# Moo_Sensors.net
KiCad netlist of a schematic drawn in Altium Designer
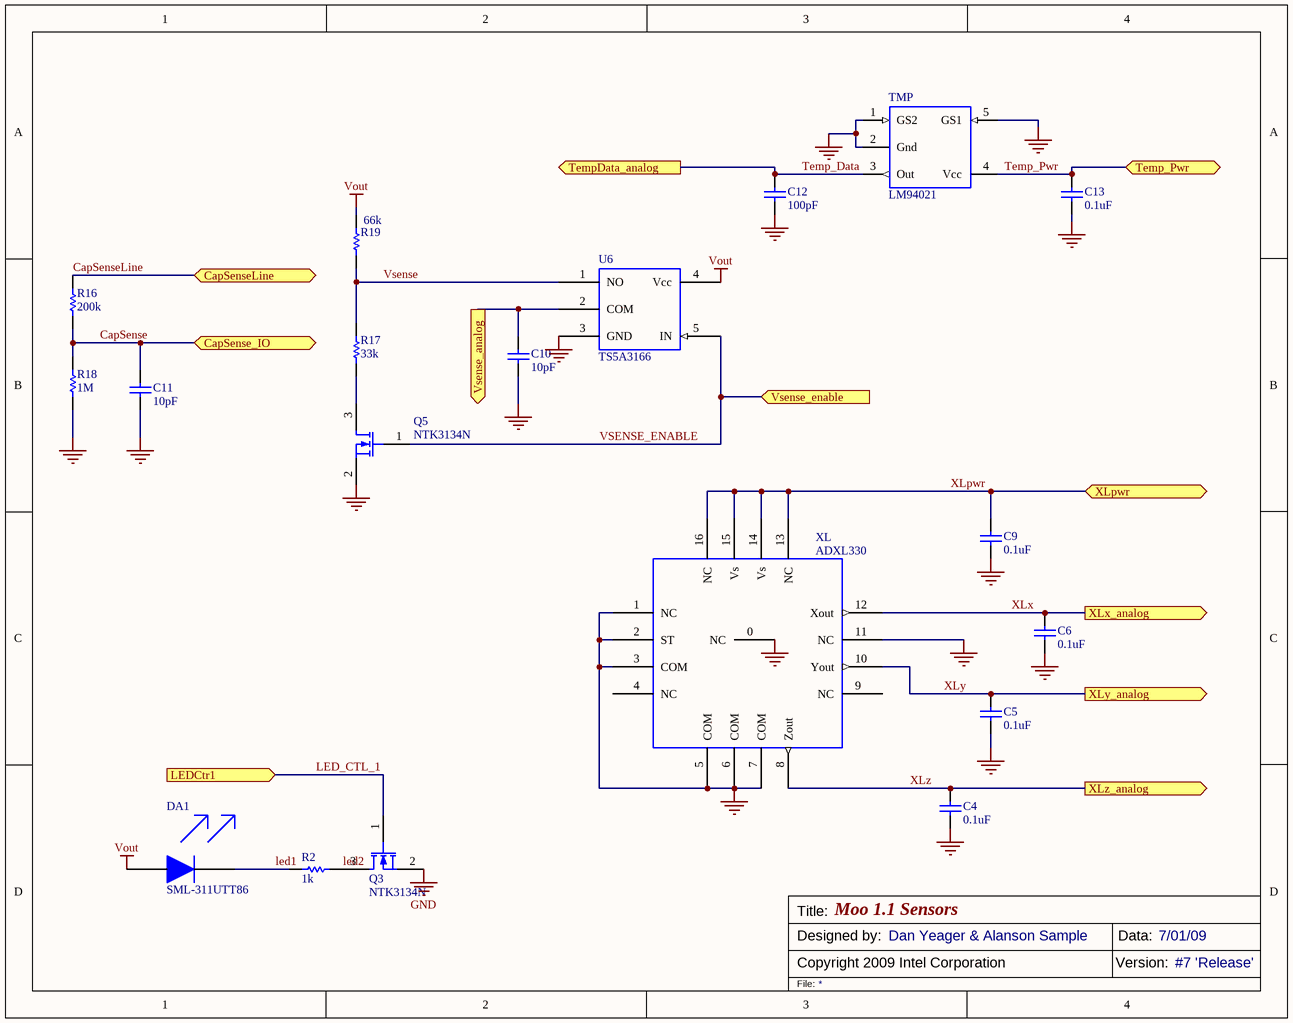
[diagram p0: Moo_Sensors.SchDoc]

(export (version "E")
  (design (tool "Eeschema 10.0.6"))
  (components
    (comp (ref "C4")
      (value "0.1uF")
      (footprint "WispLib:0402")
      (description "Ceramic Capacitor - Standard")
      (fields (field (name "Comment") "Ceramic_Chip_Capacitor"))
      (libsource (lib "WispLib") (part "Ceramic_Chip_Capacitor"))
    )
    (comp (ref "C5")
      (value "0.1uF")
      (footprint "WispLib:0402")
      (description "Ceramic Capacitor - Standard")
      (fields (field (name "Comment") "Ceramic_Chip_Capacitor"))
      (libsource (lib "WispLib") (part "Ceramic_Chip_Capacitor"))
    )
    (comp (ref "C6")
      (value "0.1uF")
      (footprint "WispLib:0402")
      (description "Ceramic Capacitor - Standard")
      (fields (field (name "Comment") "Ceramic_Chip_Capacitor"))
      (libsource (lib "WispLib") (part "Ceramic_Chip_Capacitor"))
    )
    (comp (ref "C9")
      (value "0.1uF")
      (footprint "WispLib:0402")
      (description "Ceramic Capacitor - Standard")
      (fields (field (name "Comment") "Ceramic_Chip_Capacitor"))
      (libsource (lib "WispLib") (part "Ceramic_Chip_Capacitor"))
    )
    (comp (ref "C10")
      (value "10pF")
      (footprint "WispLib:0402")
      (description "Ceramic Capacitor - Standard")
      (fields (field (name "Comment") "Ceramic_Chip_Capacitor"))
      (libsource (lib "WispLib") (part "Ceramic_Chip_Capacitor"))
    )
    (comp (ref "C11")
      (value "10pF")
      (footprint "WispLib:0402")
      (description "Ceramic Capacitor - Standard")
      (fields (field (name "Comment") "Ceramic_Chip_Capacitor"))
      (libsource (lib "WispLib") (part "Ceramic_Chip_Capacitor"))
    )
    (comp (ref "C12")
      (value "100pF")
      (footprint "WispLib:0402")
      (description "Ceramic Capacitor - Standard")
      (fields (field (name "Comment") "Ceramic_Chip_Capacitor"))
      (libsource (lib "WispLib") (part "Ceramic_Chip_Capacitor"))
    )
    (comp (ref "C13")
      (value "0.1uF")
      (footprint "WispLib:0402")
      (description "Ceramic Capacitor - Standard")
      (fields (field (name "Comment") "Ceramic_Chip_Capacitor"))
      (libsource (lib "WispLib") (part "Ceramic_Chip_Capacitor"))
    )
    (comp (ref "DA1")
      (value "SML-311UTT86")
      (footprint "LED-0603")
      (description "LED 630NM RED WTR CLR 0603 SMD")
      (libsource (lib "WispLib") (part "SML-311UTT86"))
    )
    (comp (ref "Q3")
      (value "NTK3134N")
      (footprint "SOT723")
      (description "Powe Mosfet 20V, 890mA, Single N-channel")
      (libsource (lib "WispLib") (part "NTK3134N"))
    )
    (comp (ref "Q5")
      (value "NTK3134N")
      (footprint "SOT723")
      (description "Powe Mosfet 20V, 890mA, Single N-channel")
      (libsource (lib "") (part "NTK3134N_1"))
    )
    (comp (ref "R2")
      (value "1k")
      (footprint "WispLib:0402")
      (description "Thick Film Chip Resistor")
      (libsource (lib "*") (part "Thick Film Chip Resistor"))
    )
    (comp (ref "R16")
      (value "200k")
      (footprint "WispLib:0402")
      (description "Thick Film Chip Resistor")
      (libsource (lib "*") (part "Thick Film Chip Resistor"))
    )
    (comp (ref "R17")
      (value "33k")
      (footprint "WispLib:0402")
      (description "Thick Film Chip Resistor")
      (libsource (lib "*") (part "Thick Film Chip Resistor"))
    )
    (comp (ref "R18")
      (value "1M")
      (footprint "WispLib:0402")
      (description "Thick Film Chip Resistor")
      (libsource (lib "*") (part "Thick Film Chip Resistor"))
    )
    (comp (ref "R19")
      (value "66k")
      (footprint "WispLib:0402")
      (description "Thick Film Chip Resistor")
      (libsource (lib "*") (part "Thick Film Chip Resistor"))
    )
    (comp (ref "TMP")
      (value "LM94021")
      (footprint "WispLib:SC70")
      (description "Temperature Sensor")
      (libsource (lib "*") (part "LM94021"))
    )
    (comp (ref "U6")
      (value "TS5A3166")
      (footprint "sc70-5")
      (description "TI Analog Switch 100nA 1ohm Normally Open")
      (libsource (lib "WispLib") (part "TS5A3166"))
    )
    (comp (ref "XL")
      (value "ADXL330")
      (footprint "WispLib:16-QFN")
      (description "Analog Devices 3D Accelerometer")
      (libsource (lib "*") (part "ADXL330k"))
    )
  )
  (nets
    (net (code "1") (name "/CapSense") (class "Default")
      (node (ref "C11") (pin "1") (pinfunction "1_1") (pintype "passive"))
      (node (ref "R16") (pin "2") (pinfunction "2_2") (pintype "passive"))
      (node (ref "R18") (pin "1") (pinfunction "1_1") (pintype "passive"))
    )
    (net (code "2") (name "/CapSenseLine") (class "Default")
      (node (ref "R16") (pin "1") (pinfunction "1_1") (pintype "passive"))
    )
    (net (code "3") (name "/LED_CTL_1") (class "Default")
      (node (ref "Q3") (pin "1") (pinfunction "G_1") (pintype "passive"))
    )
    (net (code "4") (name "/Temp_Data") (class "Default")
      (node (ref "C12") (pin "2") (pinfunction "2_2") (pintype "passive"))
      (node (ref "TMP") (pin "3") (pinfunction "Out_3") (pintype "output"))
    )
    (net (code "5") (name "/Temp_Pwr") (class "Default")
      (node (ref "C13") (pin "2") (pinfunction "2_2") (pintype "passive"))
      (node (ref "TMP") (pin "4") (pinfunction "Vcc_4") (pintype "power_in"))
    )
    (net (code "6") (name "/VSENSE_ENABLE") (class "Default")
      (node (ref "Q5") (pin "1") (pinfunction "G_1") (pintype "passive"))
      (node (ref "U6") (pin "5") (pinfunction "IN_5") (pintype "input"))
    )
    (net (code "7") (name "/Vsense") (class "Default")
      (node (ref "R17") (pin "1") (pinfunction "1_1") (pintype "passive"))
      (node (ref "R19") (pin "2") (pinfunction "2_2") (pintype "passive"))
      (node (ref "U6") (pin "1") (pinfunction "NO_1") (pintype "passive"))
    )
    (net (code "8") (name "/Vsense_analog") (class "Default")
      (node (ref "C10") (pin "1") (pinfunction "1_1") (pintype "passive"))
      (node (ref "U6") (pin "2") (pinfunction "COM_2") (pintype "passive"))
    )
    (net (code "9") (name "/XLpwr") (class "Default")
      (node (ref "C9") (pin "2") (pinfunction "2_2") (pintype "passive"))
      (node (ref "XL") (pin "13") (pinfunction "NC_13") (pintype "passive"))
      (node (ref "XL") (pin "14") (pinfunction "Vs_14") (pintype "power_in"))
      (node (ref "XL") (pin "15") (pinfunction "Vs_15") (pintype "power_in"))
      (node (ref "XL") (pin "16") (pinfunction "NC_16") (pintype "passive"))
    )
    (net (code "10") (name "/XLx") (class "Default")
      (node (ref "C6") (pin "1") (pinfunction "1_1") (pintype "passive"))
      (node (ref "XL") (pin "12") (pinfunction "Xout_12") (pintype "output"))
    )
    (net (code "11") (name "/XLy") (class "Default")
      (node (ref "C5") (pin "2") (pinfunction "2_2") (pintype "passive"))
      (node (ref "XL") (pin "10") (pinfunction "Yout_10") (pintype "output"))
    )
    (net (code "12") (name "/XLz") (class "Default")
      (node (ref "C4") (pin "2") (pinfunction "2_2") (pintype "passive"))
      (node (ref "XL") (pin "8") (pinfunction "Zout_8") (pintype "output"))
    )
    (net (code "13") (name "/led1") (class "Default")
      (node (ref "DA1") (pin "2") (pintype "passive"))
      (node (ref "R2") (pin "1") (pinfunction "1_1") (pintype "passive"))
    )
    (net (code "14") (name "/led2") (class "Default")
      (node (ref "Q3") (pin "3") (pinfunction "D_3") (pintype "passive"))
      (node (ref "R2") (pin "2") (pinfunction "2_2") (pintype "passive"))
    )
    (net (code "15") (name "GND") (class "Default")
      (node (ref "C10") (pin "2") (pinfunction "2_2") (pintype "passive"))
      (node (ref "C11") (pin "2") (pinfunction "2_2") (pintype "passive"))
      (node (ref "C12") (pin "1") (pinfunction "1_1") (pintype "passive"))
      (node (ref "C13") (pin "1") (pinfunction "1_1") (pintype "passive"))
      (node (ref "C4") (pin "1") (pinfunction "1_1") (pintype "passive"))
      (node (ref "C5") (pin "1") (pinfunction "1_1") (pintype "passive"))
      (node (ref "C6") (pin "2") (pinfunction "2_2") (pintype "passive"))
      (node (ref "C9") (pin "1") (pinfunction "1_1") (pintype "passive"))
      (node (ref "Q3") (pin "2") (pinfunction "S_2") (pintype "passive"))
      (node (ref "Q5") (pin "2") (pinfunction "S_2") (pintype "passive"))
      (node (ref "R18") (pin "2") (pinfunction "2_2") (pintype "passive"))
      (node (ref "TMP") (pin "1") (pinfunction "GS2_1") (pintype "input"))
      (node (ref "TMP") (pin "2") (pinfunction "Gnd_2") (pintype "power_in"))
      (node (ref "TMP") (pin "5") (pinfunction "GS1_5") (pintype "input"))
      (node (ref "U6") (pin "3") (pinfunction "GND_3") (pintype "power_in"))
      (node (ref "XL") (pin "0") (pinfunction "NC_0") (pintype "passive"))
      (node (ref "XL") (pin "1") (pinfunction "NC_1") (pintype "passive"))
      (node (ref "XL") (pin "11") (pinfunction "NC_11") (pintype "passive"))
      (node (ref "XL") (pin "2") (pinfunction "ST_2") (pintype "passive"))
      (node (ref "XL") (pin "3") (pinfunction "COM_3") (pintype "power_in"))
      (node (ref "XL") (pin "5") (pinfunction "COM_5") (pintype "power_in"))
      (node (ref "XL") (pin "6") (pinfunction "COM_6") (pintype "power_in"))
      (node (ref "XL") (pin "7") (pinfunction "COM_7") (pintype "power_in"))
    )
    (net (code "16") (name "Net-(Q5-D)") (class "Default")
      (node (ref "Q5") (pin "3") (pinfunction "D_3") (pintype "passive"))
      (node (ref "R17") (pin "2") (pinfunction "2_2") (pintype "passive"))
    )
    (net (code "17") (name "Vout") (class "Default")
      (node (ref "DA1") (pin "1") (pintype "passive"))
      (node (ref "R19") (pin "1") (pinfunction "1_1") (pintype "passive"))
      (node (ref "U6") (pin "4") (pinfunction "Vcc_4") (pintype "power_in"))
    )
    (net (code "18") (name "unconnected-(XL-NC-Pad4)") (class "Default")
      (node (ref "XL") (pin "4") (pinfunction "NC_4") (pintype "passive"))
    )
    (net (code "19") (name "unconnected-(XL-NC-Pad9)") (class "Default")
      (node (ref "XL") (pin "9") (pinfunction "NC_9") (pintype "passive"))
    )
  )
)
